# 2021-02-15_HALO_Main_Board.net
KiCad netlist of a schematic drawn in EAGLE
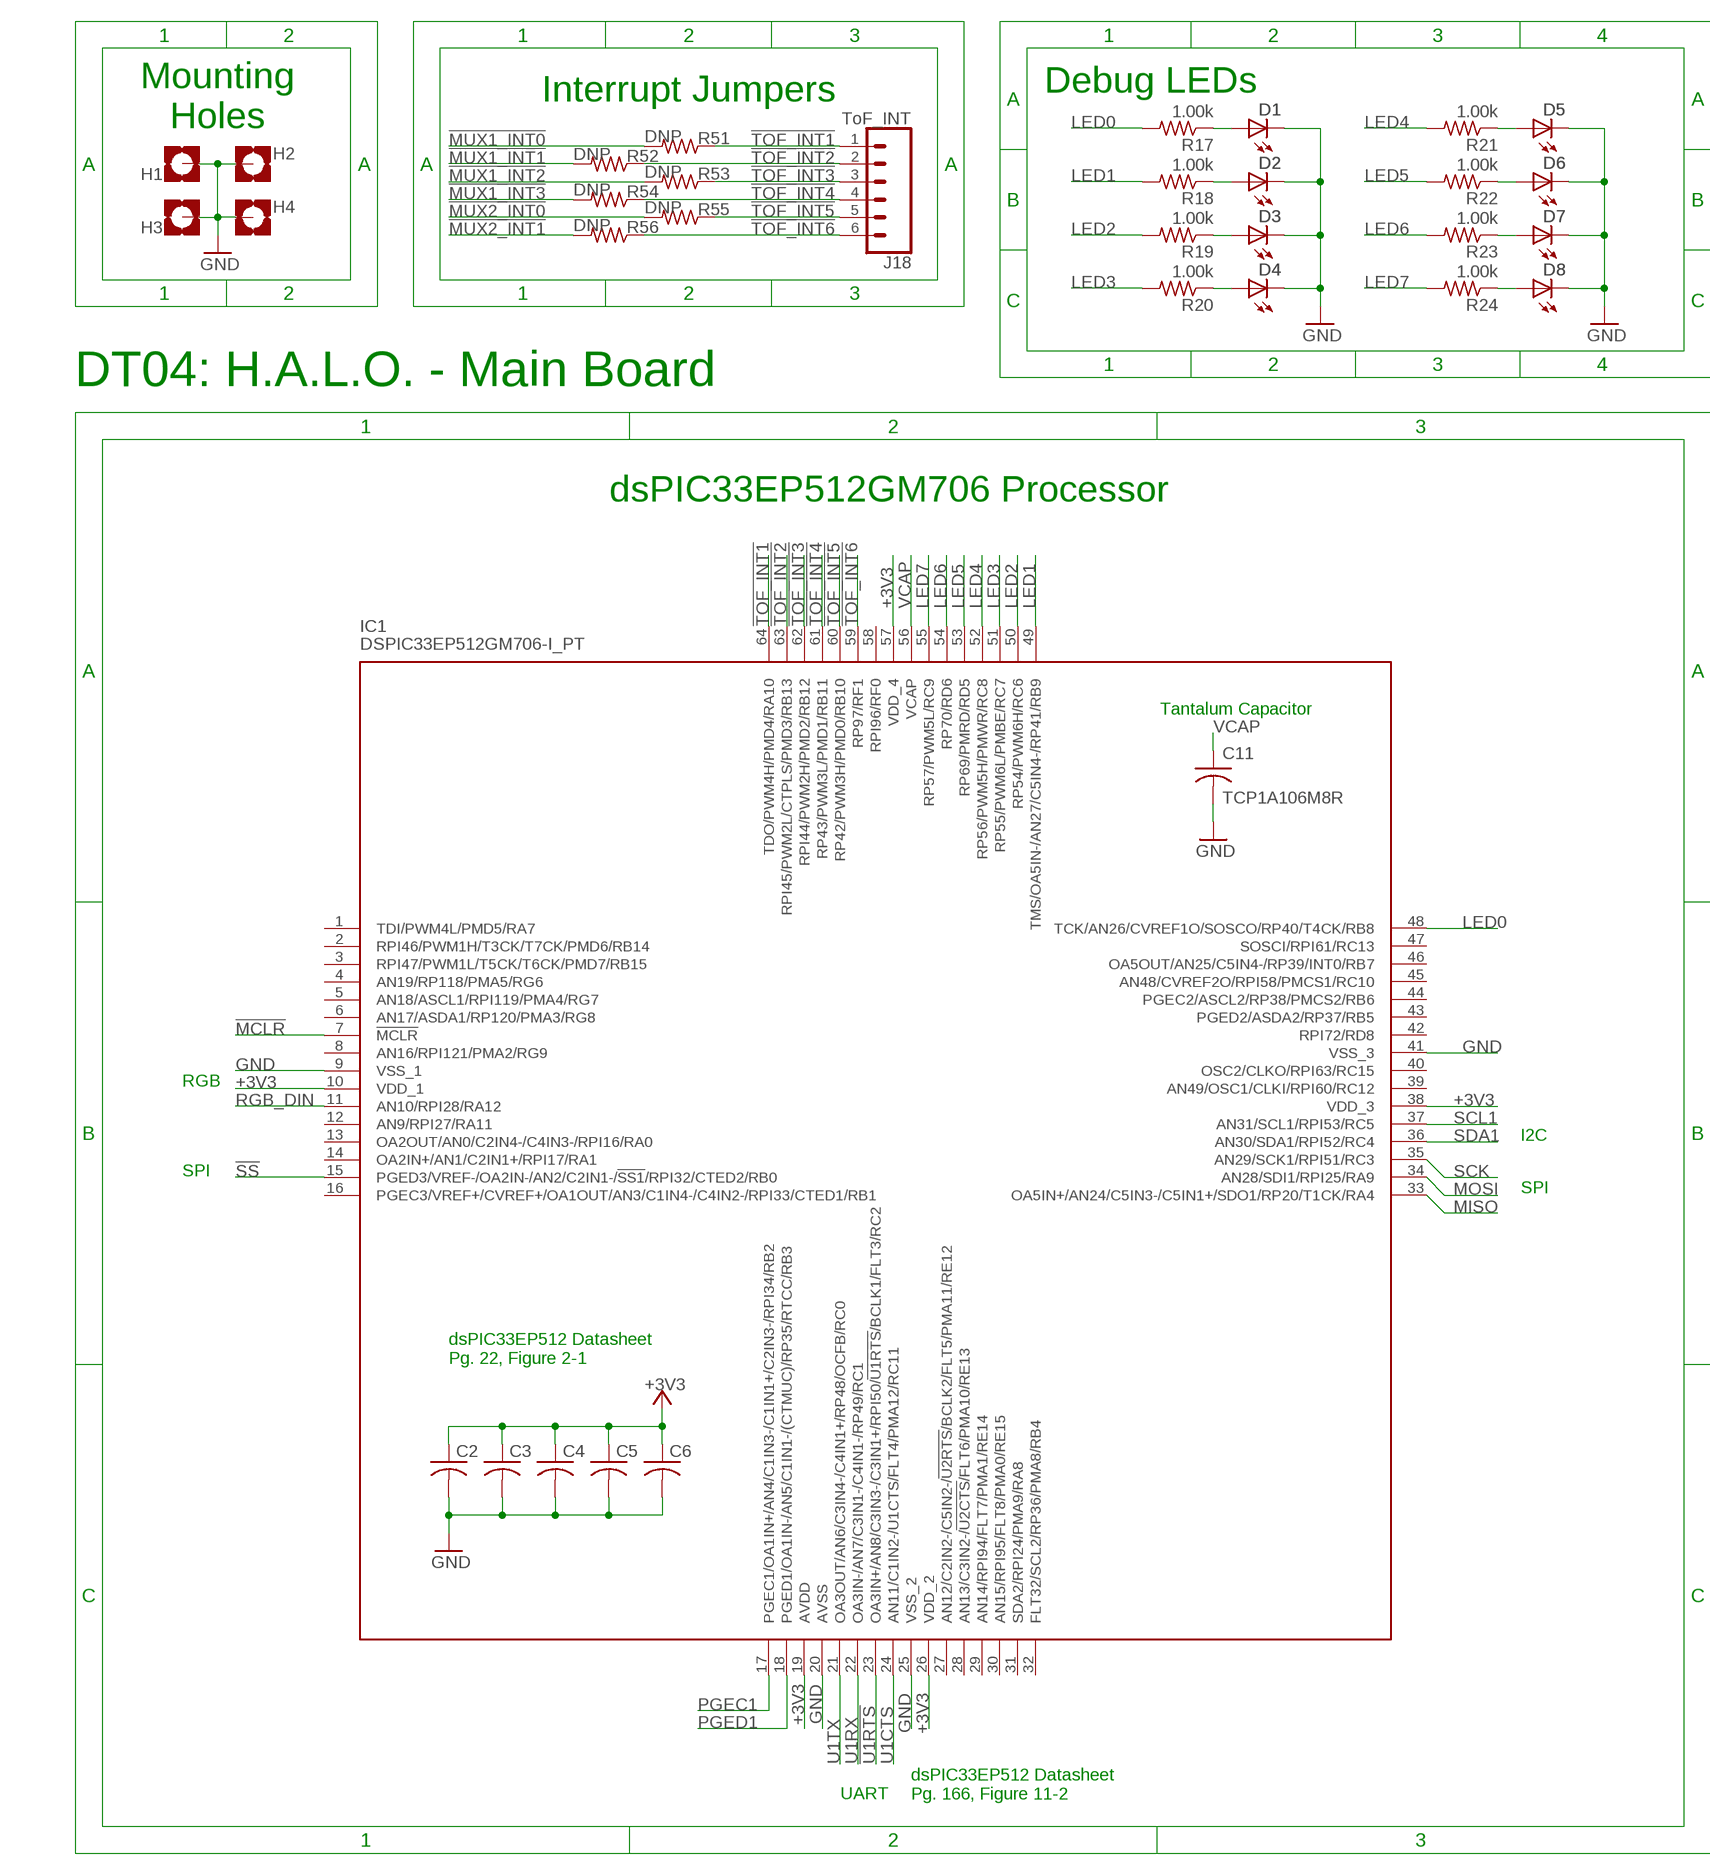
[diagram p0: schematic, sheet 1, part 1 of 2]
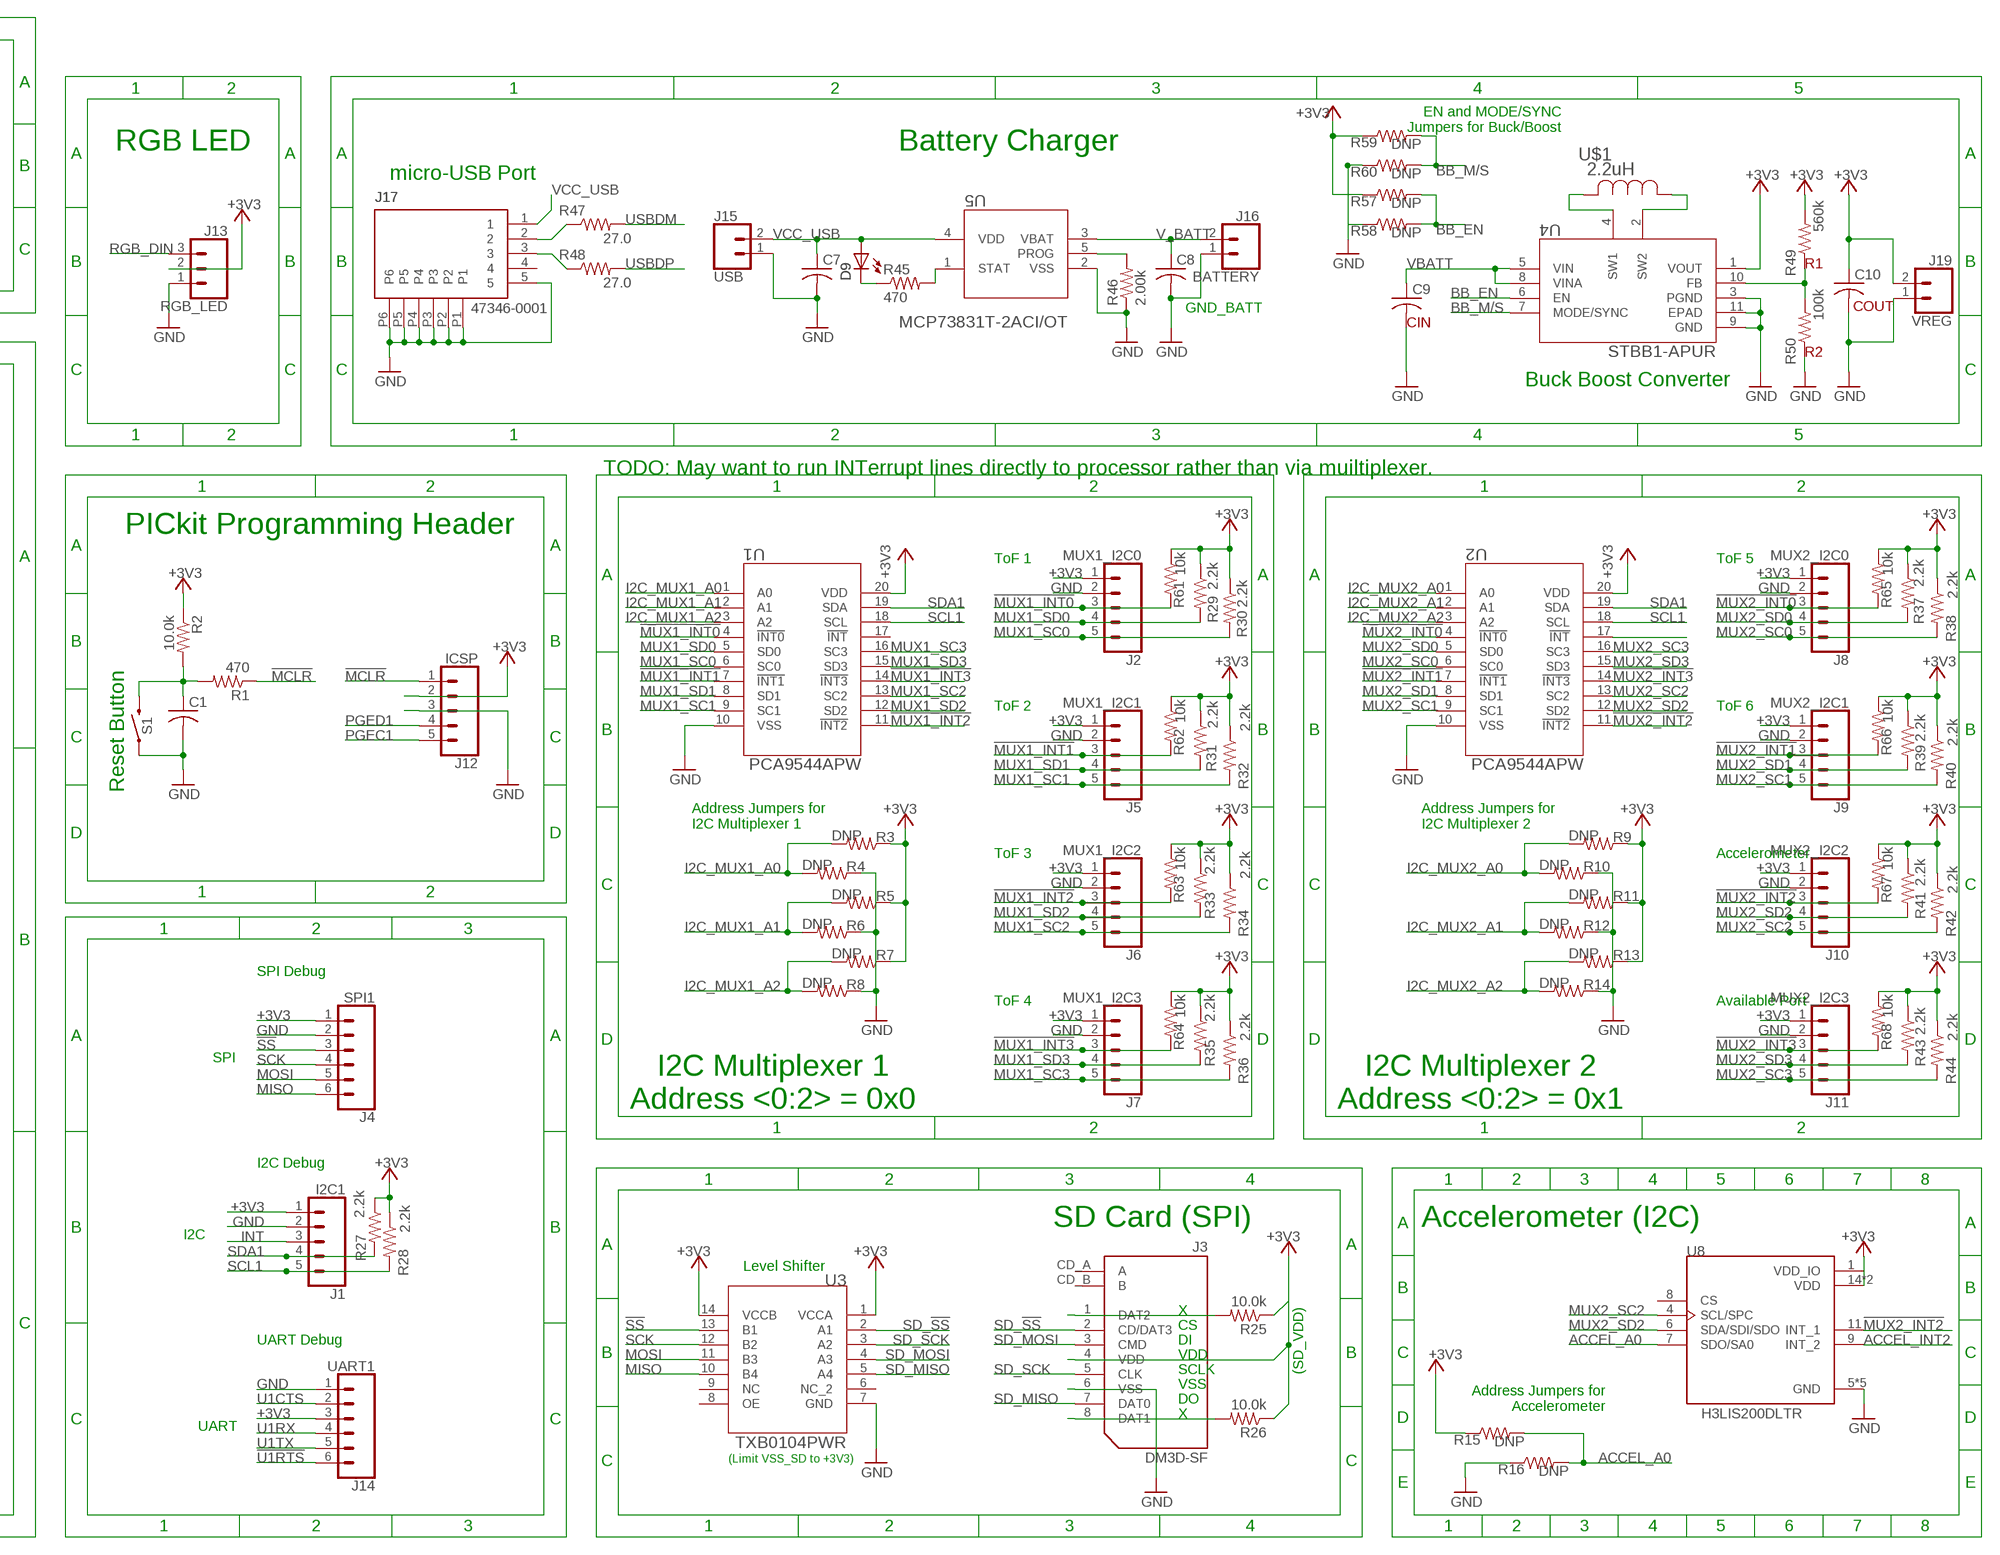
[diagram p1: schematic, sheet 1, part 2 of 2]

(export (version "E")
  (design (tool "Eeschema 10.0.6"))
  (components
    (comp (ref "C1")
      (value "0.1uF")
      (footprint "eagle-import:C0805")
      (libsource (lib "eagle-import") (part "C-USC0805"))
    )
    (comp (ref "C2")
      (value "0.1uF")
      (footprint "eagle-import:C0805")
      (libsource (lib "eagle-import") (part "C-USC0805"))
    )
    (comp (ref "C3")
      (value "0.1uF")
      (footprint "eagle-import:C0805")
      (libsource (lib "eagle-import") (part "C-USC0805"))
    )
    (comp (ref "C4")
      (value "0.1uF")
      (footprint "eagle-import:C0805")
      (libsource (lib "eagle-import") (part "C-USC0805"))
    )
    (comp (ref "C5")
      (value "0.1uF")
      (footprint "eagle-import:C0805")
      (libsource (lib "eagle-import") (part "C-USC0805"))
    )
    (comp (ref "C6")
      (value "0.1uF")
      (footprint "eagle-import:C0805")
      (libsource (lib "eagle-import") (part "C-USC0805"))
    )
    (comp (ref "C7")
      (value "4.7uF")
      (footprint "eagle-import:C0805")
      (libsource (lib "eagle-import") (part "C-USC0805"))
    )
    (comp (ref "C8")
      (value "4.7uF")
      (footprint "eagle-import:C0805")
      (libsource (lib "eagle-import") (part "C-USC0805"))
    )
    (comp (ref "C9")
      (value "10uF")
      (footprint "eagle-import:C0805")
      (libsource (lib "eagle-import") (part "C-USC0805"))
    )
    (comp (ref "C10")
      (value "22uF")
      (footprint "eagle-import:C0805")
      (libsource (lib "eagle-import") (part "C-USC0805"))
    )
    (comp (ref "C11")
      (value "TCP1A106M8R")
      (footprint "eagle-import:TCP_ROM")
      (libsource (lib "eagle-import") (part "TCP1A106M8R"))
    )
    (comp (ref "D1")
      (value "CHIP-LED0805")
      (footprint "eagle-import:CHIP-LED0805")
      (libsource (lib "eagle-import") (part "CHIP-LED0805"))
    )
    (comp (ref "D2")
      (value "CHIP-LED0805")
      (footprint "eagle-import:CHIP-LED0805")
      (libsource (lib "eagle-import") (part "CHIP-LED0805"))
    )
    (comp (ref "D3")
      (value "CHIP-LED0805")
      (footprint "eagle-import:CHIP-LED0805")
      (libsource (lib "eagle-import") (part "CHIP-LED0805"))
    )
    (comp (ref "D4")
      (value "CHIP-LED0805")
      (footprint "eagle-import:CHIP-LED0805")
      (libsource (lib "eagle-import") (part "CHIP-LED0805"))
    )
    (comp (ref "D5")
      (value "CHIP-LED0805")
      (footprint "eagle-import:CHIP-LED0805")
      (libsource (lib "eagle-import") (part "CHIP-LED0805"))
    )
    (comp (ref "D6")
      (value "CHIP-LED0805")
      (footprint "eagle-import:CHIP-LED0805")
      (libsource (lib "eagle-import") (part "CHIP-LED0805"))
    )
    (comp (ref "D7")
      (value "CHIP-LED0805")
      (footprint "eagle-import:CHIP-LED0805")
      (libsource (lib "eagle-import") (part "CHIP-LED0805"))
    )
    (comp (ref "D8")
      (value "CHIP-LED0805")
      (footprint "eagle-import:CHIP-LED0805")
      (libsource (lib "eagle-import") (part "CHIP-LED0805"))
    )
    (comp (ref "D9")
      (value "CHIP-LED0805")
      (footprint "eagle-import:CHIP-LED0805")
      (libsource (lib "eagle-import") (part "CHIP-LED0805"))
    )
    (comp (ref "H1")
      (value "MOUNT-PAD-SQUARE3.0")
      (footprint "eagle-import:3,0-PAD-SQUARE")
      (libsource (lib "eagle-import") (part "MOUNT-PAD-SQUARE3.0"))
    )
    (comp (ref "H2")
      (value "MOUNT-PAD-SQUARE3.0")
      (footprint "eagle-import:3,0-PAD-SQUARE")
      (libsource (lib "eagle-import") (part "MOUNT-PAD-SQUARE3.0"))
    )
    (comp (ref "H3")
      (value "MOUNT-PAD-SQUARE3.0")
      (footprint "eagle-import:3,0-PAD-SQUARE")
      (libsource (lib "eagle-import") (part "MOUNT-PAD-SQUARE3.0"))
    )
    (comp (ref "H4")
      (value "MOUNT-PAD-SQUARE3.0")
      (footprint "eagle-import:3,0-PAD-SQUARE")
      (libsource (lib "eagle-import") (part "MOUNT-PAD-SQUARE3.0"))
    )
    (comp (ref "IC1")
      (value "DSPIC33EP512GM706-I_PT")
      (footprint "eagle-import:QFP50P1200X1200X120-64N")
      (fields
        (field (name "ARROW_PART_NUMBER") "DSPIC33EP512GM706-I/PT")
        (field (name "MOUSER_PART_NUMBER") "579-512GM706-I/PT")
      )
      (libsource (lib "eagle-import") (part "DSPIC33EP512GM706-I_PT"))
    )
    (comp (ref "J1")
      (value "I2C1")
      (footprint "eagle-import:1X05")
      (libsource (lib "eagle-import") (part "CONN_05"))
    )
    (comp (ref "J2")
      (value "MUX1_I2C0")
      (footprint "eagle-import:1X05")
      (libsource (lib "eagle-import") (part "CONN_05"))
    )
    (comp (ref "J3")
      (value "DM3D-SF")
      (footprint "eagle-import:SD_CARD")
      (fields (field (name "PARTNO") "AS-ITM-00047"))
      (libsource (lib "eagle-import") (part "AS-ITM-00047"))
    )
    (comp (ref "J4")
      (value "SPI1")
      (footprint "eagle-import:1X06")
      (libsource (lib "eagle-import") (part "CONN_06SILK_FEMALE_PTH"))
    )
    (comp (ref "J5")
      (value "MUX1_I2C1")
      (footprint "eagle-import:1X05")
      (libsource (lib "eagle-import") (part "CONN_05"))
    )
    (comp (ref "J6")
      (value "MUX1_I2C2")
      (footprint "eagle-import:1X05")
      (libsource (lib "eagle-import") (part "CONN_05"))
    )
    (comp (ref "J7")
      (value "MUX1_I2C3")
      (footprint "eagle-import:1X05")
      (libsource (lib "eagle-import") (part "CONN_05"))
    )
    (comp (ref "J8")
      (value "MUX2_I2C0")
      (footprint "eagle-import:1X05")
      (libsource (lib "eagle-import") (part "CONN_05"))
    )
    (comp (ref "J9")
      (value "MUX2_I2C1")
      (footprint "eagle-import:1X05")
      (libsource (lib "eagle-import") (part "CONN_05"))
    )
    (comp (ref "J10")
      (value "MUX2_I2C2")
      (footprint "eagle-import:1X05")
      (libsource (lib "eagle-import") (part "CONN_05"))
    )
    (comp (ref "J11")
      (value "MUX2_I2C3")
      (footprint "eagle-import:1X05")
      (libsource (lib "eagle-import") (part "CONN_05"))
    )
    (comp (ref "J12")
      (value "ICSP")
      (footprint "eagle-import:1X05")
      (libsource (lib "eagle-import") (part "CONN_05"))
    )
    (comp (ref "J13")
      (value "RGB_LED")
      (footprint "eagle-import:1X03_LOCK")
      (libsource (lib "eagle-import") (part "CONN_03LOCK"))
    )
    (comp (ref "J14")
      (value "UART1")
      (footprint "eagle-import:1X06")
      (libsource (lib "eagle-import") (part "CONN_06SILK_FEMALE_PTH"))
    )
    (comp (ref "J15")
      (value "USB")
      (footprint "eagle-import:1X02")
      (libsource (lib "eagle-import") (part "CONN_02"))
    )
    (comp (ref "J16")
      (value "BATTERY")
      (footprint "eagle-import:1X02")
      (libsource (lib "eagle-import") (part "CONN_02"))
    )
    (comp (ref "J17")
      (value "47346-0001")
      (footprint "eagle-import:MICRO_USB")
      (fields (field (name "PARTNO") "AS-ITM-00021") (field (name "PARTNO_1") "AS-ITM-00021"))
      (libsource (lib "eagle-import") (part "AS-ITM-00021"))
    )
    (comp (ref "J18")
      (value "ToF_INT")
      (footprint "eagle-import:1X06")
      (libsource (lib "eagle-import") (part "CONN_06SILK_FEMALE_PTH"))
    )
    (comp (ref "J19")
      (value "VREG")
      (footprint "eagle-import:1X02")
      (libsource (lib "eagle-import") (part "CONN_02"))
    )
    (comp (ref "R1")
      (value "470")
      (footprint "eagle-import:R0805")
      (libsource (lib "eagle-import") (part "R-US_R0805"))
    )
    (comp (ref "R2")
      (value "10.0k")
      (footprint "eagle-import:R0805")
      (libsource (lib "eagle-import") (part "R-US_R0805"))
    )
    (comp (ref "R3")
      (value "DNP")
      (footprint "eagle-import:R0805")
      (libsource (lib "eagle-import") (part "R-US_R0805"))
    )
    (comp (ref "R4")
      (value "DNP")
      (footprint "eagle-import:R0805")
      (libsource (lib "eagle-import") (part "R-US_R0805"))
    )
    (comp (ref "R5")
      (value "DNP")
      (footprint "eagle-import:R0805")
      (libsource (lib "eagle-import") (part "R-US_R0805"))
    )
    (comp (ref "R6")
      (value "DNP")
      (footprint "eagle-import:R0805")
      (libsource (lib "eagle-import") (part "R-US_R0805"))
    )
    (comp (ref "R7")
      (value "DNP")
      (footprint "eagle-import:R0805")
      (libsource (lib "eagle-import") (part "R-US_R0805"))
    )
    (comp (ref "R8")
      (value "DNP")
      (footprint "eagle-import:R0805")
      (libsource (lib "eagle-import") (part "R-US_R0805"))
    )
    (comp (ref "R9")
      (value "DNP")
      (footprint "eagle-import:R0805")
      (libsource (lib "eagle-import") (part "R-US_R0805"))
    )
    (comp (ref "R10")
      (value "DNP")
      (footprint "eagle-import:R0805")
      (libsource (lib "eagle-import") (part "R-US_R0805"))
    )
    (comp (ref "R11")
      (value "DNP")
      (footprint "eagle-import:R0805")
      (libsource (lib "eagle-import") (part "R-US_R0805"))
    )
    (comp (ref "R12")
      (value "DNP")
      (footprint "eagle-import:R0805")
      (libsource (lib "eagle-import") (part "R-US_R0805"))
    )
    (comp (ref "R13")
      (value "DNP")
      (footprint "eagle-import:R0805")
      (libsource (lib "eagle-import") (part "R-US_R0805"))
    )
    (comp (ref "R14")
      (value "DNP")
      (footprint "eagle-import:R0805")
      (libsource (lib "eagle-import") (part "R-US_R0805"))
    )
    (comp (ref "R15")
      (value "DNP")
      (footprint "eagle-import:R0805")
      (libsource (lib "eagle-import") (part "R-US_R0805"))
    )
    (comp (ref "R16")
      (value "DNP")
      (footprint "eagle-import:R0805")
      (libsource (lib "eagle-import") (part "R-US_R0805"))
    )
    (comp (ref "R17")
      (value "1.00k")
      (footprint "eagle-import:R0805")
      (libsource (lib "eagle-import") (part "R-US_R0805"))
    )
    (comp (ref "R18")
      (value "1.00k")
      (footprint "eagle-import:R0805")
      (libsource (lib "eagle-import") (part "R-US_R0805"))
    )
    (comp (ref "R19")
      (value "1.00k")
      (footprint "eagle-import:R0805")
      (libsource (lib "eagle-import") (part "R-US_R0805"))
    )
    (comp (ref "R20")
      (value "1.00k")
      (footprint "eagle-import:R0805")
      (libsource (lib "eagle-import") (part "R-US_R0805"))
    )
    (comp (ref "R21")
      (value "1.00k")
      (footprint "eagle-import:R0805")
      (libsource (lib "eagle-import") (part "R-US_R0805"))
    )
    (comp (ref "R22")
      (value "1.00k")
      (footprint "eagle-import:R0805")
      (libsource (lib "eagle-import") (part "R-US_R0805"))
    )
    (comp (ref "R23")
      (value "1.00k")
      (footprint "eagle-import:R0805")
      (libsource (lib "eagle-import") (part "R-US_R0805"))
    )
    (comp (ref "R24")
      (value "1.00k")
      (footprint "eagle-import:R0805")
      (libsource (lib "eagle-import") (part "R-US_R0805"))
    )
    (comp (ref "R25")
      (value "10.0k")
      (footprint "eagle-import:R0805")
      (libsource (lib "eagle-import") (part "R-US_R0805"))
    )
    (comp (ref "R26")
      (value "10.0k")
      (footprint "eagle-import:R0805")
      (libsource (lib "eagle-import") (part "R-US_R0805"))
    )
    (comp (ref "R27")
      (value "2.2k")
      (footprint "eagle-import:R0805")
      (libsource (lib "eagle-import") (part "R-US_R0805"))
    )
    (comp (ref "R28")
      (value "2.2k")
      (footprint "eagle-import:R0805")
      (libsource (lib "eagle-import") (part "R-US_R0805"))
    )
    (comp (ref "R29")
      (value "2.2k")
      (footprint "eagle-import:R0805")
      (libsource (lib "eagle-import") (part "R-US_R0805"))
    )
    (comp (ref "R30")
      (value "2.2k")
      (footprint "eagle-import:R0805")
      (libsource (lib "eagle-import") (part "R-US_R0805"))
    )
    (comp (ref "R31")
      (value "2.2k")
      (footprint "eagle-import:R0805")
      (libsource (lib "eagle-import") (part "R-US_R0805"))
    )
    (comp (ref "R32")
      (value "2.2k")
      (footprint "eagle-import:R0805")
      (libsource (lib "eagle-import") (part "R-US_R0805"))
    )
    (comp (ref "R33")
      (value "2.2k")
      (footprint "eagle-import:R0805")
      (libsource (lib "eagle-import") (part "R-US_R0805"))
    )
    (comp (ref "R34")
      (value "2.2k")
      (footprint "eagle-import:R0805")
      (libsource (lib "eagle-import") (part "R-US_R0805"))
    )
    (comp (ref "R35")
      (value "2.2k")
      (footprint "eagle-import:R0805")
      (libsource (lib "eagle-import") (part "R-US_R0805"))
    )
    (comp (ref "R36")
      (value "2.2k")
      (footprint "eagle-import:R0805")
      (libsource (lib "eagle-import") (part "R-US_R0805"))
    )
    (comp (ref "R37")
      (value "2.2k")
      (footprint "eagle-import:R0805")
      (libsource (lib "eagle-import") (part "R-US_R0805"))
    )
    (comp (ref "R38")
      (value "2.2k")
      (footprint "eagle-import:R0805")
      (libsource (lib "eagle-import") (part "R-US_R0805"))
    )
    (comp (ref "R39")
      (value "2.2k")
      (footprint "eagle-import:R0805")
      (libsource (lib "eagle-import") (part "R-US_R0805"))
    )
    (comp (ref "R40")
      (value "2.2k")
      (footprint "eagle-import:R0805")
      (libsource (lib "eagle-import") (part "R-US_R0805"))
    )
    (comp (ref "R41")
      (value "2.2k")
      (footprint "eagle-import:R0805")
      (libsource (lib "eagle-import") (part "R-US_R0805"))
    )
    (comp (ref "R42")
      (value "2.2k")
      (footprint "eagle-import:R0805")
      (libsource (lib "eagle-import") (part "R-US_R0805"))
    )
    (comp (ref "R43")
      (value "2.2k")
      (footprint "eagle-import:R0805")
      (libsource (lib "eagle-import") (part "R-US_R0805"))
    )
    (comp (ref "R44")
      (value "2.2k")
      (footprint "eagle-import:R0805")
      (libsource (lib "eagle-import") (part "R-US_R0805"))
    )
    (comp (ref "R45")
      (value "470")
      (footprint "eagle-import:R0805")
      (libsource (lib "eagle-import") (part "R-US_R0805"))
    )
    (comp (ref "R46")
      (value "2.00k")
      (footprint "eagle-import:R0805")
      (libsource (lib "eagle-import") (part "R-US_R0805"))
    )
    (comp (ref "R47")
      (value "27.0")
      (footprint "eagle-import:R0805")
      (libsource (lib "eagle-import") (part "R-US_R0805"))
    )
    (comp (ref "R48")
      (value "27.0")
      (footprint "eagle-import:R0805")
      (libsource (lib "eagle-import") (part "R-US_R0805"))
    )
    (comp (ref "R49")
      (value "560k")
      (footprint "eagle-import:R0805")
      (libsource (lib "eagle-import") (part "R-US_R0805"))
    )
    (comp (ref "R50")
      (value "100k")
      (footprint "eagle-import:R0805")
      (libsource (lib "eagle-import") (part "R-US_R0805"))
    )
    (comp (ref "R51")
      (value "DNP")
      (footprint "eagle-import:R0805")
      (libsource (lib "eagle-import") (part "R-US_R0805"))
    )
    (comp (ref "R52")
      (value "DNP")
      (footprint "eagle-import:R0805")
      (libsource (lib "eagle-import") (part "R-US_R0805"))
    )
    (comp (ref "R53")
      (value "DNP")
      (footprint "eagle-import:R0805")
      (libsource (lib "eagle-import") (part "R-US_R0805"))
    )
    (comp (ref "R54")
      (value "DNP")
      (footprint "eagle-import:R0805")
      (libsource (lib "eagle-import") (part "R-US_R0805"))
    )
    (comp (ref "R55")
      (value "DNP")
      (footprint "eagle-import:R0805")
      (libsource (lib "eagle-import") (part "R-US_R0805"))
    )
    (comp (ref "R56")
      (value "DNP")
      (footprint "eagle-import:R0805")
      (libsource (lib "eagle-import") (part "R-US_R0805"))
    )
    (comp (ref "R57")
      (value "DNP")
      (footprint "eagle-import:R0805")
      (libsource (lib "eagle-import") (part "R-US_R0805"))
    )
    (comp (ref "R58")
      (value "DNP")
      (footprint "eagle-import:R0805")
      (libsource (lib "eagle-import") (part "R-US_R0805"))
    )
    (comp (ref "R59")
      (value "DNP")
      (footprint "eagle-import:R0805")
      (libsource (lib "eagle-import") (part "R-US_R0805"))
    )
    (comp (ref "R60")
      (value "DNP")
      (footprint "eagle-import:R0805")
      (libsource (lib "eagle-import") (part "R-US_R0805"))
    )
    (comp (ref "R61")
      (value "10k")
      (footprint "eagle-import:R0805")
      (libsource (lib "eagle-import") (part "R-US_R0805"))
    )
    (comp (ref "R62")
      (value "10k")
      (footprint "eagle-import:R0805")
      (libsource (lib "eagle-import") (part "R-US_R0805"))
    )
    (comp (ref "R63")
      (value "10k")
      (footprint "eagle-import:R0805")
      (libsource (lib "eagle-import") (part "R-US_R0805"))
    )
    (comp (ref "R64")
      (value "10k")
      (footprint "eagle-import:R0805")
      (libsource (lib "eagle-import") (part "R-US_R0805"))
    )
    (comp (ref "R65")
      (value "10k")
      (footprint "eagle-import:R0805")
      (libsource (lib "eagle-import") (part "R-US_R0805"))
    )
    (comp (ref "R66")
      (value "10k")
      (footprint "eagle-import:R0805")
      (libsource (lib "eagle-import") (part "R-US_R0805"))
    )
    (comp (ref "R67")
      (value "10k")
      (footprint "eagle-import:R0805")
      (libsource (lib "eagle-import") (part "R-US_R0805"))
    )
    (comp (ref "R68")
      (value "10k")
      (footprint "eagle-import:R0805")
      (libsource (lib "eagle-import") (part "R-US_R0805"))
    )
    (comp (ref "S1")
      (value "SWITCH-MOMENTARY-2SMD-4")
      (footprint "eagle-import:TACTILE_SWITCH_TALL")
      (libsource (lib "eagle-import") (part "SWITCH-MOMENTARY-2SMD-4"))
    )
    (comp (ref "U$1")
      (value "2.2uH")
      (footprint "eagle-import:IND_4028_TDK")
      (libsource (lib "eagle-import") (part "IND"))
    )
    (comp (ref "U1")
      (value "PCA9544APW")
      (footprint "eagle-import:SOT360-1_NXP")
      (libsource (lib "eagle-import") (part "PCA9544APW"))
    )
    (comp (ref "U2")
      (value "PCA9544APW")
      (footprint "eagle-import:SOT360-1_NXP")
      (libsource (lib "eagle-import") (part "PCA9544APW"))
    )
    (comp (ref "U3")
      (value "TXB0104PWR")
      (footprint "eagle-import:PW14")
      (fields
        (field (name "GENERIC_PART_NUMBER") "TXB0104")
        (field (name "MANUFACTURER") "Texas Instruments")
      )
      (libsource (lib "eagle-import") (part "TXB0104PWR"))
    )
    (comp (ref "U4")
      (value "STBB1-APUR")
      (footprint "eagle-import:SON_B1-APUR_STM")
      (libsource (lib "eagle-import") (part "STBB1-APUR"))
    )
    (comp (ref "U5")
      (value "MCP73831T-2ACI/OT")
      (footprint "eagle-import:SOT-23-5_MC_MCH")
      (libsource (lib "eagle-import") (part "MCP73831T-2ACI/OT"))
    )
    (comp (ref "U8")
      (value "H3LIS200DLTR")
      (footprint "eagle-import:PQFN50P300X300X100-16N")
      (fields (field (name "DIGI-KEY_PART_NUMBER") "497-15698-1-ND") (field (name "MF") "STMicroelectronics"))
      (libsource (lib "eagle-import") (part "H3LIS200DLTR"))
    )
  )
  (nets
    (net (code "1") (name "+3V3") (class "Default")
      (node (ref "C10") (pin "1") (pinfunction "1_1") (pintype "passive"))
      (node (ref "C2") (pin "1") (pinfunction "1_1") (pintype "passive"))
      (node (ref "C3") (pin "1") (pinfunction "1_1") (pintype "passive"))
      (node (ref "C4") (pin "1") (pinfunction "1_1") (pintype "passive"))
      (node (ref "C5") (pin "1") (pinfunction "1_1") (pintype "passive"))
      (node (ref "C6") (pin "1") (pinfunction "1_1") (pintype "passive"))
      (node (ref "IC1") (pin "10") (pinfunction "VDD_1_10") (pintype "bidirectional"))
      (node (ref "IC1") (pin "19") (pinfunction "AVDD_19") (pintype "bidirectional"))
      (node (ref "IC1") (pin "26") (pinfunction "VDD_2_26") (pintype "bidirectional"))
      (node (ref "IC1") (pin "38") (pinfunction "VDD_3_38") (pintype "bidirectional"))
      (node (ref "IC1") (pin "57") (pinfunction "VDD_4_57") (pintype "bidirectional"))
      (node (ref "J1") (pin "1") (pinfunction "1_1") (pintype "passive"))
      (node (ref "J10") (pin "1") (pinfunction "1_1") (pintype "passive"))
      (node (ref "J11") (pin "1") (pinfunction "1_1") (pintype "passive"))
      (node (ref "J12") (pin "2") (pinfunction "2_2") (pintype "passive"))
      (node (ref "J13") (pin "2") (pinfunction "2_2") (pintype "passive"))
      (node (ref "J14") (pin "3") (pinfunction "3_3") (pintype "passive"))
      (node (ref "J19") (pin "2") (pinfunction "2_2") (pintype "passive"))
      (node (ref "J2") (pin "1") (pinfunction "1_1") (pintype "passive"))
      (node (ref "J3") (pin "4") (pinfunction "VDD_4") (pintype "bidirectional"))
      (node (ref "J4") (pin "1") (pinfunction "1_1") (pintype "passive"))
      (node (ref "J5") (pin "1") (pinfunction "1_1") (pintype "passive"))
      (node (ref "J6") (pin "1") (pinfunction "1_1") (pintype "passive"))
      (node (ref "J7") (pin "1") (pinfunction "1_1") (pintype "passive"))
      (node (ref "J8") (pin "1") (pinfunction "1_1") (pintype "passive"))
      (node (ref "J9") (pin "1") (pinfunction "1_1") (pintype "passive"))
      (node (ref "R11") (pin "1") (pinfunction "1_1") (pintype "passive"))
      (node (ref "R13") (pin "1") (pinfunction "1_1") (pintype "passive"))
      (node (ref "R15") (pin "1") (pinfunction "1_1") (pintype "passive"))
      (node (ref "R2") (pin "1") (pinfunction "1_1") (pintype "passive"))
      (node (ref "R25") (pin "1") (pinfunction "1_1") (pintype "passive"))
      (node (ref "R26") (pin "1") (pinfunction "1_1") (pintype "passive"))
      (node (ref "R27") (pin "1") (pinfunction "1_1") (pintype "passive"))
      (node (ref "R28") (pin "1") (pinfunction "1_1") (pintype "passive"))
      (node (ref "R29") (pin "1") (pinfunction "1_1") (pintype "passive"))
      (node (ref "R3") (pin "1") (pinfunction "1_1") (pintype "passive"))
      (node (ref "R30") (pin "1") (pinfunction "1_1") (pintype "passive"))
      (node (ref "R31") (pin "1") (pinfunction "1_1") (pintype "passive"))
      (node (ref "R32") (pin "1") (pinfunction "1_1") (pintype "passive"))
      (node (ref "R33") (pin "1") (pinfunction "1_1") (pintype "passive"))
      (node (ref "R34") (pin "1") (pinfunction "1_1") (pintype "passive"))
      (node (ref "R35") (pin "1") (pinfunction "1_1") (pintype "passive"))
      (node (ref "R36") (pin "1") (pinfunction "1_1") (pintype "passive"))
      (node (ref "R37") (pin "1") (pinfunction "1_1") (pintype "passive"))
      (node (ref "R38") (pin "1") (pinfunction "1_1") (pintype "passive"))
      (node (ref "R39") (pin "1") (pinfunction "1_1") (pintype "passive"))
      (node (ref "R40") (pin "1") (pinfunction "1_1") (pintype "passive"))
      (node (ref "R41") (pin "1") (pinfunction "1_1") (pintype "passive"))
      (node (ref "R42") (pin "1") (pinfunction "1_1") (pintype "passive"))
      (node (ref "R43") (pin "1") (pinfunction "1_1") (pintype "passive"))
      (node (ref "R44") (pin "1") (pinfunction "1_1") (pintype "passive"))
      (node (ref "R49") (pin "2") (pinfunction "2_2") (pintype "passive"))
      (node (ref "R5") (pin "1") (pinfunction "1_1") (pintype "passive"))
      (node (ref "R57") (pin "1") (pinfunction "1_1") (pintype "passive"))
      (node (ref "R59") (pin "1") (pinfunction "1_1") (pintype "passive"))
      (node (ref "R61") (pin "1") (pinfunction "1_1") (pintype "passive"))
      (node (ref "R62") (pin "1") (pinfunction "1_1") (pintype "passive"))
      (node (ref "R63") (pin "1") (pinfunction "1_1") (pintype "passive"))
      (node (ref "R64") (pin "1") (pinfunction "1_1") (pintype "passive"))
      (node (ref "R65") (pin "1") (pinfunction "1_1") (pintype "passive"))
      (node (ref "R66") (pin "1") (pinfunction "1_1") (pintype "passive"))
      (node (ref "R67") (pin "1") (pinfunction "1_1") (pintype "passive"))
      (node (ref "R68") (pin "1") (pinfunction "1_1") (pintype "passive"))
      (node (ref "R7") (pin "1") (pinfunction "1_1") (pintype "passive"))
      (node (ref "R9") (pin "1") (pinfunction "1_1") (pintype "passive"))
      (node (ref "U1") (pin "20") (pinfunction "VDD_20") (pintype "passive"))
      (node (ref "U2") (pin "20") (pinfunction "VDD_20") (pintype "passive"))
      (node (ref "U3") (pin "1") (pinfunction "VCCA_1") (pintype "power_in"))
      (node (ref "U3") (pin "14") (pinfunction "VCCB_14") (pintype "power_in"))
      (node (ref "U4") (pin "1") (pinfunction "VOUT_1") (pintype "power_in"))
      (node (ref "U8") (pin "1") (pinfunction "VDD_IO_1") (pintype "power_in"))
      (node (ref "U8") (pin "14") (pinfunction "VDD_14") (pintype "power_in"))
      (node (ref "U8") (pin "15") (pinfunction "VDD_15") (pintype "power_in"))
    )
    (net (code "2") (name "/ACCEL_A0") (class "Default")
      (node (ref "R15") (pin "2") (pinfunction "2_2") (pintype "passive"))
      (node (ref "R16") (pin "2") (pinfunction "2_2") (pintype "passive"))
      (node (ref "U8") (pin "7") (pinfunction "SDO/SA0_7") (pintype "output"))
    )
    (net (code "3") (name "/ACCEL_INT2") (class "Default")
      (node (ref "U8") (pin "9") (pinfunction "INT_2_9") (pintype "output"))
    )
    (net (code "4") (name "/BB_EN") (class "Default")
      (node (ref "R57") (pin "2") (pinfunction "2_2") (pintype "passive"))
      (node (ref "R58") (pin "2") (pinfunction "2_2") (pintype "passive"))
      (node (ref "U4") (pin "6") (pinfunction "EN_6") (pintype "passive"))
    )
    (net (code "5") (name "/BB_M{slash}S") (class "Default")
      (node (ref "R59") (pin "2") (pinfunction "2_2") (pintype "passive"))
      (node (ref "R60") (pin "2") (pinfunction "2_2") (pintype "passive"))
      (node (ref "U4") (pin "7") (pinfunction "MODE/SYNC_7") (pintype "passive"))
    )
    (net (code "6") (name "/I2C_MUX1_A0") (class "Default")
      (node (ref "R3") (pin "2") (pinfunction "2_2") (pintype "passive"))
      (node (ref "R4") (pin "2") (pinfunction "2_2") (pintype "passive"))
      (node (ref "U1") (pin "1") (pinfunction "A0_1") (pintype "passive"))
    )
    (net (code "7") (name "/I2C_MUX1_A1") (class "Default")
      (node (ref "R5") (pin "2") (pinfunction "2_2") (pintype "passive"))
      (node (ref "R6") (pin "2") (pinfunction "2_2") (pintype "passive"))
      (node (ref "U1") (pin "2") (pinfunction "A1_2") (pintype "passive"))
    )
    (net (code "8") (name "/I2C_MUX1_A2") (class "Default")
      (node (ref "R7") (pin "2") (pinfunction "2_2") (pintype "passive"))
      (node (ref "R8") (pin "2") (pinfunction "2_2") (pintype "passive"))
      (node (ref "U1") (pin "3") (pinfunction "A2_3") (pintype "passive"))
    )
    (net (code "9") (name "/I2C_MUX2_A0") (class "Default")
      (node (ref "R10") (pin "2") (pinfunction "2_2") (pintype "passive"))
      (node (ref "R9") (pin "2") (pinfunction "2_2") (pintype "passive"))
      (node (ref "U2") (pin "1") (pinfunction "A0_1") (pintype "passive"))
    )
    (net (code "10") (name "/I2C_MUX2_A1") (class "Default")
      (node (ref "R11") (pin "2") (pinfunction "2_2") (pintype "passive"))
      (node (ref "R12") (pin "2") (pinfunction "2_2") (pintype "passive"))
      (node (ref "U2") (pin "2") (pinfunction "A1_2") (pintype "passive"))
    )
    (net (code "11") (name "/I2C_MUX2_A2") (class "Default")
      (node (ref "R13") (pin "2") (pinfunction "2_2") (pintype "passive"))
      (node (ref "R14") (pin "2") (pinfunction "2_2") (pintype "passive"))
      (node (ref "U2") (pin "3") (pinfunction "A2_3") (pintype "passive"))
    )
    (net (code "12") (name "/INT") (class "Default")
      (node (ref "J1") (pin "3") (pinfunction "3_3") (pintype "passive"))
    )
    (net (code "13") (name "/LED0") (class "Default")
      (node (ref "IC1") (pin "48") (pinfunction "TCK/AN26/CVREF1O/SOSCO/RP40/T4CK/RB8_48") (pintype "bidirectional"))
      (node (ref "R17") (pin "2") (pinfunction "2_2") (pintype "passive"))
    )
    (net (code "14") (name "/LED1") (class "Default")
      (node (ref "IC1") (pin "49") (pinfunction "TMS/OA5IN-/AN27/C5IN4-/RP41/RB9_49") (pintype "bidirectional"))
      (node (ref "R18") (pin "2") (pinfunction "2_2") (pintype "passive"))
    )
    (net (code "15") (name "/LED2") (class "Default")
      (node (ref "IC1") (pin "50") (pinfunction "RP54/PWM6H/RC6_50") (pintype "bidirectional"))
      (node (ref "R19") (pin "2") (pinfunction "2_2") (pintype "passive"))
    )
    (net (code "16") (name "/LED3") (class "Default")
      (node (ref "IC1") (pin "51") (pinfunction "RP55/PWM6L/PMBE/RC7_51") (pintype "bidirectional"))
      (node (ref "R20") (pin "2") (pinfunction "2_2") (pintype "passive"))
    )
    (net (code "17") (name "/LED4") (class "Default")
      (node (ref "IC1") (pin "52") (pinfunction "RP56/PWM5H/PMWR/RC8_52") (pintype "bidirectional"))
      (node (ref "R21") (pin "2") (pinfunction "2_2") (pintype "passive"))
    )
    (net (code "18") (name "/LED5") (class "Default")
      (node (ref "IC1") (pin "53") (pinfunction "RP69/PMRD/RD5_53") (pintype "bidirectional"))
      (node (ref "R22") (pin "2") (pinfunction "2_2") (pintype "passive"))
    )
    (net (code "19") (name "/LED6") (class "Default")
      (node (ref "IC1") (pin "54") (pinfunction "RP70/RD6_54") (pintype "bidirectional"))
      (node (ref "R23") (pin "2") (pinfunction "2_2") (pintype "passive"))
    )
    (net (code "20") (name "/LED7") (class "Default")
      (node (ref "IC1") (pin "55") (pinfunction "RP57/PWM5L/RC9_55") (pintype "bidirectional"))
      (node (ref "R24") (pin "2") (pinfunction "2_2") (pintype "passive"))
    )
    (net (code "21") (name "/MISO") (class "Default")
      (node (ref "IC1") (pin "33") (pinfunction "OA5IN+/AN24/C5IN3-/C5IN1+/SDO1/RP20/T1CK/RA4_33") (pintype "bidirectional"))
      (node (ref "J4") (pin "6") (pinfunction "6_6") (pintype "passive"))
      (node (ref "U3") (pin "10") (pinfunction "B4_10") (pintype "bidirectional"))
    )
    (net (code "22") (name "/MOSI") (class "Default")
      (node (ref "IC1") (pin "34") (pinfunction "AN28/SDI1/RPI25/RA9_34") (pintype "bidirectional"))
      (node (ref "J4") (pin "5") (pinfunction "5_5") (pintype "passive"))
      (node (ref "U3") (pin "11") (pinfunction "B3_11") (pintype "bidirectional"))
    )
    (net (code "23") (name "/MUX1_SC0") (class "Default")
      (node (ref "J2") (pin "5") (pinfunction "5_5") (pintype "passive"))
      (node (ref "R30") (pin "2") (pinfunction "2_2") (pintype "passive"))
      (node (ref "U1") (pin "6") (pinfunction "SC0_6") (pintype "passive"))
    )
    (net (code "24") (name "/MUX1_SC1") (class "Default")
      (node (ref "J5") (pin "5") (pinfunction "5_5") (pintype "passive"))
      (node (ref "R32") (pin "2") (pinfunction "2_2") (pintype "passive"))
      (node (ref "U1") (pin "9") (pinfunction "SC1_9") (pintype "passive"))
    )
    (net (code "25") (name "/MUX1_SC2") (class "Default")
      (node (ref "J6") (pin "5") (pinfunction "5_5") (pintype "passive"))
      (node (ref "R34") (pin "2") (pinfunction "2_2") (pintype "passive"))
      (node (ref "U1") (pin "13") (pinfunction "SC2_13") (pintype "passive"))
    )
    (net (code "26") (name "/MUX1_SC3") (class "Default")
      (node (ref "J7") (pin "5") (pinfunction "5_5") (pintype "passive"))
      (node (ref "R36") (pin "2") (pinfunction "2_2") (pintype "passive"))
      (node (ref "U1") (pin "16") (pinfunction "SC3_16") (pintype "passive"))
    )
    (net (code "27") (name "/MUX1_SD0") (class "Default")
      (node (ref "J2") (pin "4") (pinfunction "4_4") (pintype "passive"))
      (node (ref "R29") (pin "2") (pinfunction "2_2") (pintype "passive"))
      (node (ref "U1") (pin "5") (pinfunction "SD0_5") (pintype "passive"))
    )
    (net (code "28") (name "/MUX1_SD1") (class "Default")
      (node (ref "J5") (pin "4") (pinfunction "4_4") (pintype "passive"))
      (node (ref "R31") (pin "2") (pinfunction "2_2") (pintype "passive"))
      (node (ref "U1") (pin "8") (pinfunction "SD1_8") (pintype "passive"))
    )
    (net (code "29") (name "/MUX1_SD2") (class "Default")
      (node (ref "J6") (pin "4") (pinfunction "4_4") (pintype "passive"))
      (node (ref "R33") (pin "2") (pinfunction "2_2") (pintype "passive"))
      (node (ref "U1") (pin "12") (pinfunction "SD2_12") (pintype "passive"))
    )
    (net (code "30") (name "/MUX1_SD3") (class "Default")
      (node (ref "J7") (pin "4") (pinfunction "4_4") (pintype "passive"))
      (node (ref "R35") (pin "2") (pinfunction "2_2") (pintype "passive"))
      (node (ref "U1") (pin "15") (pinfunction "SD3_15") (pintype "passive"))
    )
    (net (code "31") (name "/MUX2_SC0") (class "Default")
      (node (ref "J8") (pin "5") (pinfunction "5_5") (pintype "passive"))
      (node (ref "R38") (pin "2") (pinfunction "2_2") (pintype "passive"))
      (node (ref "U2") (pin "6") (pinfunction "SC0_6") (pintype "passive"))
    )
    (net (code "32") (name "/MUX2_SC1") (class "Default")
      (node (ref "J9") (pin "5") (pinfunction "5_5") (pintype "passive"))
      (node (ref "R40") (pin "2") (pinfunction "2_2") (pintype "passive"))
      (node (ref "U2") (pin "9") (pinfunction "SC1_9") (pintype "passive"))
    )
    (net (code "33") (name "/MUX2_SC2") (class "Default")
      (node (ref "J10") (pin "5") (pinfunction "5_5") (pintype "passive"))
      (node (ref "R42") (pin "2") (pinfunction "2_2") (pintype "passive"))
      (node (ref "U2") (pin "13") (pinfunction "SC2_13") (pintype "passive"))
      (node (ref "U8") (pin "4") (pinfunction "SCL/SPC_4") (pintype "input"))
    )
    (net (code "34") (name "/MUX2_SC3") (class "Default")
      (node (ref "J11") (pin "5") (pinfunction "5_5") (pintype "passive"))
      (node (ref "R44") (pin "2") (pinfunction "2_2") (pintype "passive"))
      (node (ref "U2") (pin "16") (pinfunction "SC3_16") (pintype "passive"))
    )
    (net (code "35") (name "/MUX2_SD0") (class "Default")
      (node (ref "J8") (pin "4") (pinfunction "4_4") (pintype "passive"))
      (node (ref "R37") (pin "2") (pinfunction "2_2") (pintype "passive"))
      (node (ref "U2") (pin "5") (pinfunction "SD0_5") (pintype "passive"))
    )
    (net (code "36") (name "/MUX2_SD1") (class "Default")
      (node (ref "J9") (pin "4") (pinfunction "4_4") (pintype "passive"))
      (node (ref "R39") (pin "2") (pinfunction "2_2") (pintype "passive"))
      (node (ref "U2") (pin "8") (pinfunction "SD1_8") (pintype "passive"))
    )
    (net (code "37") (name "/MUX2_SD2") (class "Default")
      (node (ref "J10") (pin "4") (pinfunction "4_4") (pintype "passive"))
      (node (ref "R41") (pin "2") (pinfunction "2_2") (pintype "passive"))
      (node (ref "U2") (pin "12") (pinfunction "SD2_12") (pintype "passive"))
      (node (ref "U8") (pin "6") (pinfunction "SDA/SDI/SDO_6") (pintype "bidirectional"))
    )
    (net (code "38") (name "/MUX2_SD3") (class "Default")
      (node (ref "J11") (pin "4") (pinfunction "4_4") (pintype "passive"))
      (node (ref "R43") (pin "2") (pinfunction "2_2") (pintype "passive"))
      (node (ref "U2") (pin "15") (pinfunction "SD3_15") (pintype "passive"))
    )
    (net (code "39") (name "/PGEC1") (class "Default")
      (node (ref "IC1") (pin "17") (pinfunction "PGEC1/OA1IN+/AN4/C1IN3-/C1IN1+/C2IN3-/RPI34/RB2_17") (pintype "bidirectional"))
      (node (ref "J12") (pin "5") (pinfunction "5_5") (pintype "passive"))
    )
    (net (code "40") (name "/PGED1") (class "Default")
      (node (ref "IC1") (pin "18") (pinfunction "PGED1/OA1IN-/AN5/C1IN1-/(CTMUC)/RP35/RTCC/RB3_18") (pintype "bidirectional"))
      (node (ref "J12") (pin "4") (pinfunction "4_4") (pintype "passive"))
    )
    (net (code "41") (name "/RGB_DIN") (class "Default")
      (node (ref "IC1") (pin "11") (pinfunction "AN10/RPI28/RA12_11") (pintype "bidirectional"))
      (node (ref "J13") (pin "3") (pinfunction "3_3") (pintype "passive"))
    )
    (net (code "42") (name "/SCK") (class "Default")
      (node (ref "IC1") (pin "35") (pinfunction "AN29/SCK1/RPI51/RC3_35") (pintype "bidirectional"))
      (node (ref "J4") (pin "4") (pinfunction "4_4") (pintype "passive"))
      (node (ref "U3") (pin "12") (pinfunction "B2_12") (pintype "bidirectional"))
    )
    (net (code "43") (name "/SCL1") (class "Default")
      (node (ref "IC1") (pin "37") (pinfunction "AN31/SCL1/RPI53/RC5_37") (pintype "bidirectional"))
      (node (ref "J1") (pin "5") (pinfunction "5_5") (pintype "passive"))
      (node (ref "R28") (pin "2") (pinfunction "2_2") (pintype "passive"))
      (node (ref "U1") (pin "18") (pinfunction "SCL_18") (pintype "passive"))
      (node (ref "U2") (pin "18") (pinfunction "SCL_18") (pintype "passive"))
    )
    (net (code "44") (name "/SDA1") (class "Default")
      (node (ref "IC1") (pin "36") (pinfunction "AN30/SDA1/RPI52/RC4_36") (pintype "bidirectional"))
      (node (ref "J1") (pin "4") (pinfunction "4_4") (pintype "passive"))
      (node (ref "R27") (pin "2") (pinfunction "2_2") (pintype "passive"))
      (node (ref "U1") (pin "19") (pinfunction "SDA_19") (pintype "passive"))
      (node (ref "U2") (pin "19") (pinfunction "SDA_19") (pintype "passive"))
    )
    (net (code "45") (name "/SD_MISO") (class "Default")
      (node (ref "J3") (pin "7") (pinfunction "DAT0_7") (pintype "bidirectional"))
      (node (ref "U3") (pin "5") (pinfunction "A4_5") (pintype "bidirectional"))
    )
    (net (code "46") (name "/SD_MOSI") (class "Default")
      (node (ref "J3") (pin "3") (pinfunction "CMD_3") (pintype "bidirectional"))
      (node (ref "U3") (pin "4") (pinfunction "A3_4") (pintype "bidirectional"))
    )
    (net (code "47") (name "/SD_SCK") (class "Default")
      (node (ref "J3") (pin "5") (pinfunction "CLK_5") (pintype "bidirectional"))
      (node (ref "U3") (pin "3") (pinfunction "A2_3") (pintype "bidirectional"))
    )
    (net (code "48") (name "/SD_~{SS}") (class "Default")
      (node (ref "J3") (pin "2") (pinfunction "CD/DAT3_2") (pintype "bidirectional"))
      (node (ref "U3") (pin "2") (pinfunction "A1_2") (pintype "bidirectional"))
    )
    (net (code "49") (name "/U1CTS") (class "Default")
      (node (ref "IC1") (pin "24") (pinfunction "AN11/C1IN2-/U1CTS/FLT4/PMA12/RC11_24") (pintype "bidirectional"))
      (node (ref "J14") (pin "2") (pinfunction "2_2") (pintype "passive"))
    )
    (net (code "50") (name "/U1RX") (class "Default")
      (node (ref "IC1") (pin "22") (pinfunction "OA3IN-/AN7/C3IN1-/C4IN1-/RP49/RC1_22") (pintype "bidirectional"))
      (node (ref "J14") (pin "4") (pinfunction "4_4") (pintype "passive"))
    )
    (net (code "51") (name "/U1TX") (class "Default")
      (node (ref "IC1") (pin "21") (pinfunction "OA3OUT/AN6/C3IN4-/C4IN1+/RP48/OCFB/RC0_21") (pintype "bidirectional"))
      (node (ref "J14") (pin "5") (pinfunction "5_5") (pintype "passive"))
    )
    (net (code "52") (name "/USBDM") (class "Default")
      (node (ref "R47") (pin "2") (pinfunction "2_2") (pintype "passive"))
    )
    (net (code "53") (name "/USBDP") (class "Default")
      (node (ref "R48") (pin "2") (pinfunction "2_2") (pintype "passive"))
    )
    (net (code "54") (name "/VBATT") (class "Default")
      (node (ref "C9") (pin "1") (pinfunction "1_1") (pintype "passive"))
      (node (ref "U4") (pin "5") (pinfunction "VIN_5") (pintype "power_in"))
      (node (ref "U4") (pin "8") (pinfunction "VINA_8") (pintype "power_in"))
    )
    (net (code "55") (name "/VCAP") (class "Default")
      (node (ref "C11") (pin "1") (pinfunction "1_1") (pintype "passive"))
      (node (ref "IC1") (pin "56") (pinfunction "VCAP_56") (pintype "bidirectional"))
    )
    (net (code "56") (name "/VCC_USB") (class "Default")
      (node (ref "C7") (pin "1") (pinfunction "1_1") (pintype "passive"))
      (node (ref "D9") (pin "A") (pinfunction "A_A") (pintype "passive"))
      (node (ref "J15") (pin "2") (pinfunction "2_2") (pintype "passive"))
      (node (ref "J17") (pin "1") (pinfunction "1_1") (pintype "bidirectional"))
      (node (ref "U5") (pin "4") (pinfunction "VDD_4") (pintype "passive"))
    )
    (net (code "57") (name "/V_BATT") (class "Default")
      (node (ref "C8") (pin "1") (pinfunction "1_1") (pintype "passive"))
      (node (ref "J16") (pin "2") (pinfunction "2_2") (pintype "passive"))
      (node (ref "U5") (pin "3") (pinfunction "VBAT_3") (pintype "passive"))
    )
    (net (code "58") (name "/~{MCLR}") (class "Default")
      (node (ref "IC1") (pin "7") (pinfunction "~{MCLR}_7") (pintype "bidirectional"))
      (node (ref "J12") (pin "1") (pinfunction "1_1") (pintype "passive"))
      (node (ref "R1") (pin "1") (pinfunction "1_1") (pintype "passive"))
    )
    (net (code "59") (name "/~{MUX1_INT0}") (class "Default")
      (node (ref "J2") (pin "3") (pinfunction "3_3") (pintype "passive"))
      (node (ref "R51") (pin "2") (pinfunction "2_2") (pintype "passive"))
      (node (ref "R61") (pin "2") (pinfunction "2_2") (pintype "passive"))
      (node (ref "U1") (pin "4") (pinfunction "~{INT0}_4") (pintype "passive"))
    )
    (net (code "60") (name "/~{MUX1_INT1}") (class "Default")
      (node (ref "J5") (pin "3") (pinfunction "3_3") (pintype "passive"))
      (node (ref "R52") (pin "2") (pinfunction "2_2") (pintype "passive"))
      (node (ref "R62") (pin "2") (pinfunction "2_2") (pintype "passive"))
      (node (ref "U1") (pin "7") (pinfunction "~{INT1}_7") (pintype "passive"))
    )
    (net (code "61") (name "/~{MUX1_INT2}") (class "Default")
      (node (ref "J6") (pin "3") (pinfunction "3_3") (pintype "passive"))
      (node (ref "R53") (pin "2") (pinfunction "2_2") (pintype "passive"))
      (node (ref "R63") (pin "2") (pinfunction "2_2") (pintype "passive"))
      (node (ref "U1") (pin "11") (pinfunction "~{INT2}_11") (pintype "passive"))
    )
    (net (code "62") (name "/~{MUX1_INT3}") (class "Default")
      (node (ref "J7") (pin "3") (pinfunction "3_3") (pintype "passive"))
      (node (ref "R54") (pin "2") (pinfunction "2_2") (pintype "passive"))
      (node (ref "R64") (pin "2") (pinfunction "2_2") (pintype "passive"))
      (node (ref "U1") (pin "14") (pinfunction "~{INT3}_14") (pintype "passive"))
    )
    (net (code "63") (name "/~{MUX2_INT0}") (class "Default")
      (node (ref "J8") (pin "3") (pinfunction "3_3") (pintype "passive"))
      (node (ref "R55") (pin "2") (pinfunction "2_2") (pintype "passive"))
      (node (ref "R65") (pin "2") (pinfunction "2_2") (pintype "passive"))
      (node (ref "U2") (pin "4") (pinfunction "~{INT0}_4") (pintype "passive"))
    )
    (net (code "64") (name "/~{MUX2_INT1}") (class "Default")
      (node (ref "J9") (pin "3") (pinfunction "3_3") (pintype "passive"))
      (node (ref "R56") (pin "2") (pinfunction "2_2") (pintype "passive"))
      (node (ref "R66") (pin "2") (pinfunction "2_2") (pintype "passive"))
      (node (ref "U2") (pin "7") (pinfunction "~{INT1}_7") (pintype "passive"))
    )
    (net (code "65") (name "/~{MUX2_INT2}") (class "Default")
      (node (ref "J10") (pin "3") (pinfunction "3_3") (pintype "passive"))
      (node (ref "R67") (pin "2") (pinfunction "2_2") (pintype "passive"))
      (node (ref "U2") (pin "11") (pinfunction "~{INT2}_11") (pintype "passive"))
      (node (ref "U8") (pin "11") (pinfunction "INT_1_11") (pintype "output"))
    )
    (net (code "66") (name "/~{MUX2_INT3}") (class "Default")
      (node (ref "J11") (pin "3") (pinfunction "3_3") (pintype "passive"))
      (node (ref "R68") (pin "2") (pinfunction "2_2") (pintype "passive"))
      (node (ref "U2") (pin "14") (pinfunction "~{INT3}_14") (pintype "passive"))
    )
    (net (code "67") (name "/~{SS}") (class "Default")
      (node (ref "IC1") (pin "15") (pinfunction "PGED3/VREF-/OA2IN-/AN2/C2IN1-/~{SS1}/RPI32/CTED2/RB0_15") (pintype "bidirectional"))
      (node (ref "J4") (pin "3") (pinfunction "3_3") (pintype "passive"))
      (node (ref "U3") (pin "13") (pinfunction "B1_13") (pintype "bidirectional"))
    )
    (net (code "68") (name "/~{TOF_INT1}") (class "Default")
      (node (ref "IC1") (pin "64") (pinfunction "TDO/PWM4H/PMD4/RA10_64") (pintype "bidirectional"))
      (node (ref "J18") (pin "1") (pinfunction "1_1") (pintype "passive"))
      (node (ref "R51") (pin "1") (pinfunction "1_1") (pintype "passive"))
    )
    (net (code "69") (name "/~{TOF_INT2}") (class "Default")
      (node (ref "IC1") (pin "63") (pinfunction "RPI45/PWM2L/CTPLS/PMD3/RB13_63") (pintype "bidirectional"))
      (node (ref "J18") (pin "2") (pinfunction "2_2") (pintype "passive"))
      (node (ref "R52") (pin "1") (pinfunction "1_1") (pintype "passive"))
    )
    (net (code "70") (name "/~{TOF_INT3}") (class "Default")
      (node (ref "IC1") (pin "62") (pinfunction "RPI44/PWM2H/PMD2/RB12_62") (pintype "bidirectional"))
      (node (ref "J18") (pin "3") (pinfunction "3_3") (pintype "passive"))
      (node (ref "R53") (pin "1") (pinfunction "1_1") (pintype "passive"))
    )
    (net (code "71") (name "/~{TOF_INT4}") (class "Default")
      (node (ref "IC1") (pin "61") (pinfunction "RP43/PWM3L/PMD1/RB11_61") (pintype "bidirectional"))
      (node (ref "J18") (pin "4") (pinfunction "4_4") (pintype "passive"))
      (node (ref "R54") (pin "1") (pinfunction "1_1") (pintype "passive"))
    )
    (net (code "72") (name "/~{TOF_INT5}") (class "Default")
      (node (ref "IC1") (pin "60") (pinfunction "RP42/PWM3H/PMD0/RB10_60") (pintype "bidirectional"))
      (node (ref "J18") (pin "5") (pinfunction "5_5") (pintype "passive"))
      (node (ref "R55") (pin "1") (pinfunction "1_1") (pintype "passive"))
    )
    (net (code "73") (name "/~{TOF_INT6}") (class "Default")
      (node (ref "IC1") (pin "59") (pinfunction "RP97/RF1_59") (pintype "bidirectional"))
      (node (ref "J18") (pin "6") (pinfunction "6_6") (pintype "passive"))
      (node (ref "R56") (pin "1") (pinfunction "1_1") (pintype "passive"))
    )
    (net (code "74") (name "/~{U1RTS}") (class "Default")
      (node (ref "IC1") (pin "23") (pinfunction "OA3IN+/AN8/C3IN3-/C3IN1+/RPI50/~{U1RTS}/BCLK1/FLT3/RC2_23") (pintype "bidirectional"))
      (node (ref "J14") (pin "6") (pinfunction "6_6") (pintype "passive"))
    )
    (net (code "75") (name "GND") (class "Default")
      (node (ref "C1") (pin "2") (pinfunction "2_2") (pintype "passive"))
      (node (ref "C10") (pin "2") (pinfunction "2_2") (pintype "passive"))
      (node (ref "C11") (pin "2") (pinfunction "2_2") (pintype "passive"))
      (node (ref "C2") (pin "2") (pinfunction "2_2") (pintype "passive"))
      (node (ref "C3") (pin "2") (pinfunction "2_2") (pintype "passive"))
      (node (ref "C4") (pin "2") (pinfunction "2_2") (pintype "passive"))
      (node (ref "C5") (pin "2") (pinfunction "2_2") (pintype "passive"))
      (node (ref "C6") (pin "2") (pinfunction "2_2") (pintype "passive"))
      (node (ref "C7") (pin "2") (pinfunction "2_2") (pintype "passive"))
      (node (ref "C8") (pin "2") (pinfunction "2_2") (pintype "passive"))
      (node (ref "C9") (pin "2") (pinfunction "2_2") (pintype "passive"))
      (node (ref "D1") (pin "C") (pinfunction "C_C") (pintype "passive"))
      (node (ref "D2") (pin "C") (pinfunction "C_C") (pintype "passive"))
      (node (ref "D3") (pin "C") (pinfunction "C_C") (pintype "passive"))
      (node (ref "D4") (pin "C") (pinfunction "C_C") (pintype "passive"))
      (node (ref "D5") (pin "C") (pinfunction "C_C") (pintype "passive"))
      (node (ref "D6") (pin "C") (pinfunction "C_C") (pintype "passive"))
      (node (ref "D7") (pin "C") (pinfunction "C_C") (pintype "passive"))
      (node (ref "D8") (pin "C") (pinfunction "C_C") (pintype "passive"))
      (node (ref "H1") (pin "B3,0") (pinfunction "MOUNT_B3,0") (pintype "passive"))
      (node (ref "H2") (pin "B3,0") (pinfunction "MOUNT_B3,0") (pintype "passive"))
      (node (ref "H3") (pin "B3,0") (pinfunction "MOUNT_B3,0") (pintype "passive"))
      (node (ref "H4") (pin "B3,0") (pinfunction "MOUNT_B3,0") (pintype "passive"))
      (node (ref "IC1") (pin "20") (pinfunction "AVSS_20") (pintype "bidirectional"))
      (node (ref "IC1") (pin "25") (pinfunction "VSS_2_25") (pintype "bidirectional"))
      (node (ref "IC1") (pin "41") (pinfunction "VSS_3_41") (pintype "bidirectional"))
      (node (ref "IC1") (pin "9") (pinfunction "VSS_1_9") (pintype "bidirectional"))
      (node (ref "J1") (pin "2") (pinfunction "2_2") (pintype "passive"))
      (node (ref "J10") (pin "2") (pinfunction "2_2") (pintype "passive"))
      (node (ref "J11") (pin "2") (pinfunction "2_2") (pintype "passive"))
      (node (ref "J12") (pin "3") (pinfunction "3_3") (pintype "passive"))
      (node (ref "J13") (pin "1") (pinfunction "1_1") (pintype "passive"))
      (node (ref "J14") (pin "1") (pinfunction "1_1") (pintype "passive"))
      (node (ref "J15") (pin "1") (pinfunction "1_1") (pintype "passive"))
      (node (ref "J16") (pin "1") (pinfunction "1_1") (pintype "passive"))
      (node (ref "J17") (pin "5") (pinfunction "5_5") (pintype "bidirectional"))
      (node (ref "J17") (pin "P1") (pinfunction "P1_P1") (pintype "bidirectional"))
      (node (ref "J17") (pin "P2") (pinfunction "P2_P2") (pintype "bidirectional"))
      (node (ref "J17") (pin "P3") (pinfunction "P3_P3") (pintype "bidirectional"))
      (node (ref "J17") (pin "P4") (pinfunction "P4_P4") (pintype "bidirectional"))
      (node (ref "J17") (pin "P5") (pinfunction "P5_P5") (pintype "bidirectional"))
      (node (ref "J17") (pin "P6") (pinfunction "P6_P6") (pintype "bidirectional"))
      (node (ref "J19") (pin "1") (pinfunction "1_1") (pintype "passive"))
      (node (ref "J2") (pin "2") (pinfunction "2_2") (pintype "passive"))
      (node (ref "J3") (pin "6") (pinfunction "VSS_6") (pintype "bidirectional"))
      (node (ref "J4") (pin "2") (pinfunction "2_2") (pintype "passive"))
      (node (ref "J5") (pin "2") (pinfunction "2_2") (pintype "passive"))
      (node (ref "J6") (pin "2") (pinfunction "2_2") (pintype "passive"))
      (node (ref "J7") (pin "2") (pinfunction "2_2") (pintype "passive"))
      (node (ref "J8") (pin "2") (pinfunction "2_2") (pintype "passive"))
      (node (ref "J9") (pin "2") (pinfunction "2_2") (pintype "passive"))
      (node (ref "R10") (pin "1") (pinfunction "1_1") (pintype "passive"))
      (node (ref "R12") (pin "1") (pinfunction "1_1") (pintype "passive"))
      (node (ref "R14") (pin "1") (pinfunction "1_1") (pintype "passive"))
      (node (ref "R16") (pin "1") (pinfunction "1_1") (pintype "passive"))
      (node (ref "R4") (pin "1") (pinfunction "1_1") (pintype "passive"))
      (node (ref "R46") (pin "1") (pinfunction "1_1") (pintype "passive"))
      (node (ref "R50") (pin "1") (pinfunction "1_1") (pintype "passive"))
      (node (ref "R58") (pin "1") (pinfunction "1_1") (pintype "passive"))
      (node (ref "R6") (pin "1") (pinfunction "1_1") (pintype "passive"))
      (node (ref "R60") (pin "1") (pinfunction "1_1") (pintype "passive"))
      (node (ref "R8") (pin "1") (pinfunction "1_1") (pintype "passive"))
      (node (ref "S1") (pin "A2") (pinfunction "1_A2") (pintype "passive"))
      (node (ref "U1") (pin "10") (pinfunction "VSS_10") (pintype "passive"))
      (node (ref "U2") (pin "10") (pinfunction "VSS_10") (pintype "passive"))
      (node (ref "U3") (pin "7") (pinfunction "GND_7") (pintype "power_in"))
      (node (ref "U4") (pin "11") (pinfunction "EPAD_11") (pintype "passive"))
      (node (ref "U4") (pin "3") (pinfunction "PGND_3") (pintype "passive"))
      (node (ref "U4") (pin "9") (pinfunction "GND_9") (pintype "passive"))
      (node (ref "U5") (pin "2") (pinfunction "VSS_2") (pintype "passive"))
      (node (ref "U8") (pin "10") (pinfunction "GND_10") (pintype "power_in"))
      (node (ref "U8") (pin "12") (pinfunction "GND_12") (pintype "power_in"))
      (node (ref "U8") (pin "13") (pinfunction "GND_13") (pintype "power_in"))
      (node (ref "U8") (pin "16") (pinfunction "GND_16") (pintype "power_in"))
      (node (ref "U8") (pin "5") (pinfunction "GND_5") (pintype "power_in"))
    )
    (net (code "76") (name "Net-(D1-PadA)") (class "Default")
      (node (ref "D1") (pin "A") (pinfunction "A_A") (pintype "passive"))
      (node (ref "R17") (pin "1") (pinfunction "1_1") (pintype "passive"))
    )
    (net (code "77") (name "Net-(D2-PadA)") (class "Default")
      (node (ref "D2") (pin "A") (pinfunction "A_A") (pintype "passive"))
      (node (ref "R18") (pin "1") (pinfunction "1_1") (pintype "passive"))
    )
    (net (code "78") (name "Net-(D3-PadA)") (class "Default")
      (node (ref "D3") (pin "A") (pinfunction "A_A") (pintype "passive"))
      (node (ref "R19") (pin "1") (pinfunction "1_1") (pintype "passive"))
    )
    (net (code "79") (name "Net-(D4-PadA)") (class "Default")
      (node (ref "D4") (pin "A") (pinfunction "A_A") (pintype "passive"))
      (node (ref "R20") (pin "1") (pinfunction "1_1") (pintype "passive"))
    )
    (net (code "80") (name "Net-(D5-PadA)") (class "Default")
      (node (ref "D5") (pin "A") (pinfunction "A_A") (pintype "passive"))
      (node (ref "R21") (pin "1") (pinfunction "1_1") (pintype "passive"))
    )
    (net (code "81") (name "Net-(D6-PadA)") (class "Default")
      (node (ref "D6") (pin "A") (pinfunction "A_A") (pintype "passive"))
      (node (ref "R22") (pin "1") (pinfunction "1_1") (pintype "passive"))
    )
    (net (code "82") (name "Net-(D7-PadA)") (class "Default")
      (node (ref "D7") (pin "A") (pinfunction "A_A") (pintype "passive"))
      (node (ref "R23") (pin "1") (pinfunction "1_1") (pintype "passive"))
    )
    (net (code "83") (name "Net-(D8-PadA)") (class "Default")
      (node (ref "D8") (pin "A") (pinfunction "A_A") (pintype "passive"))
      (node (ref "R24") (pin "1") (pinfunction "1_1") (pintype "passive"))
    )
    (net (code "84") (name "Net-(D9-PadC)") (class "Default")
      (node (ref "D9") (pin "C") (pinfunction "C_C") (pintype "passive"))
      (node (ref "R45") (pin "1") (pinfunction "1_1") (pintype "passive"))
    )
    (net (code "85") (name "Net-(J3-DAT1)") (class "Default")
      (node (ref "J3") (pin "8") (pinfunction "DAT1_8") (pintype "bidirectional"))
      (node (ref "R26") (pin "2") (pinfunction "2_2") (pintype "passive"))
    )
    (net (code "86") (name "Net-(J3-DAT2)") (class "Default")
      (node (ref "J3") (pin "1") (pinfunction "DAT2_1") (pintype "bidirectional"))
      (node (ref "R25") (pin "2") (pinfunction "2_2") (pintype "passive"))
    )
    (net (code "87") (name "Net-(J17-Pad2)") (class "Default")
      (node (ref "J17") (pin "2") (pinfunction "2_2") (pintype "bidirectional"))
      (node (ref "R47") (pin "1") (pinfunction "1_1") (pintype "passive"))
    )
    (net (code "88") (name "Net-(J17-Pad3)") (class "Default")
      (node (ref "J17") (pin "3") (pinfunction "3_3") (pintype "bidirectional"))
      (node (ref "R48") (pin "1") (pinfunction "1_1") (pintype "passive"))
    )
    (net (code "89") (name "Net-(S1-2)") (class "Default")
      (node (ref "C1") (pin "1") (pinfunction "1_1") (pintype "passive"))
      (node (ref "R1") (pin "2") (pinfunction "2_2") (pintype "passive"))
      (node (ref "R2") (pin "2") (pinfunction "2_2") (pintype "passive"))
      (node (ref "S1") (pin "B2") (pinfunction "2_B2") (pintype "passive"))
    )
    (net (code "90") (name "Net-(U4-FB)") (class "Default")
      (node (ref "R49") (pin "1") (pinfunction "1_1") (pintype "passive"))
      (node (ref "R50") (pin "2") (pinfunction "2_2") (pintype "passive"))
      (node (ref "U4") (pin "10") (pinfunction "FB_10") (pintype "passive"))
    )
    (net (code "91") (name "Net-(U4-SW1)") (class "Default")
      (node (ref "U$1") (pin "2") (pinfunction "2_2") (pintype "passive"))
      (node (ref "U4") (pin "4") (pinfunction "SW1_4") (pintype "bidirectional"))
    )
    (net (code "92") (name "Net-(U4-SW2)") (class "Default")
      (node (ref "U$1") (pin "1") (pinfunction "1_1") (pintype "passive"))
      (node (ref "U4") (pin "2") (pinfunction "SW2_2") (pintype "bidirectional"))
    )
    (net (code "93") (name "Net-(U5-PROG)") (class "Default")
      (node (ref "R46") (pin "2") (pinfunction "2_2") (pintype "passive"))
      (node (ref "U5") (pin "5") (pinfunction "PROG_5") (pintype "passive"))
    )
    (net (code "94") (name "Net-(U5-STAT)") (class "Default")
      (node (ref "R45") (pin "2") (pinfunction "2_2") (pintype "passive"))
      (node (ref "U5") (pin "1") (pinfunction "STAT_1") (pintype "passive"))
    )
    (net (code "95") (name "unconnected-(IC1-AN9{slash}RPI27{slash}RA11-Pad12)") (class "Default")
      (node (ref "IC1") (pin "12") (pinfunction "AN9/RPI27/RA11_12") (pintype "bidirectional"))
    )
    (net (code "96") (name "unconnected-(IC1-AN12{slash}C2IN2-{slash}C5IN2-{slash}~{U2RTS}{slash}BCLK2{slash}FLT5{slash}PMA11{slash}RE12-Pad27)") (class "Default")
      (node (ref "IC1") (pin "27") (pinfunction "AN12/C2IN2-/C5IN2-/~{U2RTS}/BCLK2/FLT5/PMA11/RE12_27") (pintype "bidirectional"))
    )
    (net (code "97") (name "unconnected-(IC1-AN13{slash}C3IN2-{slash}~{U2CTS}{slash}FLT6{slash}PMA10{slash}RE13-Pad28)") (class "Default")
      (node (ref "IC1") (pin "28") (pinfunction "AN13/C3IN2-/~{U2CTS}/FLT6/PMA10/RE13_28") (pintype "bidirectional"))
    )
    (net (code "98") (name "unconnected-(IC1-AN14{slash}RPI94{slash}FLT7{slash}PMA1{slash}RE14-Pad29)") (class "Default")
      (node (ref "IC1") (pin "29") (pinfunction "AN14/RPI94/FLT7/PMA1/RE14_29") (pintype "bidirectional"))
    )
    (net (code "99") (name "unconnected-(IC1-AN15{slash}RPI95{slash}FLT8{slash}PMA0{slash}RE15-Pad30)") (class "Default")
      (node (ref "IC1") (pin "30") (pinfunction "AN15/RPI95/FLT8/PMA0/RE15_30") (pintype "bidirectional"))
    )
    (net (code "100") (name "unconnected-(IC1-AN16{slash}RPI121{slash}PMA2{slash}RG9-Pad8)") (class "Default")
      (node (ref "IC1") (pin "8") (pinfunction "AN16/RPI121/PMA2/RG9_8") (pintype "bidirectional"))
    )
    (net (code "101") (name "unconnected-(IC1-AN17{slash}ASDA1{slash}RP120{slash}PMA3{slash}RG8-Pad6)") (class "Default")
      (node (ref "IC1") (pin "6") (pinfunction "AN17/ASDA1/RP120/PMA3/RG8_6") (pintype "bidirectional"))
    )
    (net (code "102") (name "unconnected-(IC1-AN18{slash}ASCL1{slash}RPI119{slash}PMA4{slash}RG7-Pad5)") (class "Default")
      (node (ref "IC1") (pin "5") (pinfunction "AN18/ASCL1/RPI119/PMA4/RG7_5") (pintype "bidirectional"))
    )
    (net (code "103") (name "unconnected-(IC1-AN19{slash}RP118{slash}PMA5{slash}RG6-Pad4)") (class "Default")
      (node (ref "IC1") (pin "4") (pinfunction "AN19/RP118/PMA5/RG6_4") (pintype "bidirectional"))
    )
    (net (code "104") (name "unconnected-(IC1-AN48{slash}CVREF2O{slash}RPI58{slash}PMCS1{slash}RC10-Pad45)") (class "Default")
      (node (ref "IC1") (pin "45") (pinfunction "AN48/CVREF2O/RPI58/PMCS1/RC10_45") (pintype "bidirectional"))
    )
    (net (code "105") (name "unconnected-(IC1-AN49{slash}OSC1{slash}CLKI{slash}RPI60{slash}RC12-Pad39)") (class "Default")
      (node (ref "IC1") (pin "39") (pinfunction "AN49/OSC1/CLKI/RPI60/RC12_39") (pintype "bidirectional"))
    )
    (net (code "106") (name "unconnected-(IC1-FLT32{slash}SCL2{slash}RP36{slash}PMA8{slash}RB4-Pad32)") (class "Default")
      (node (ref "IC1") (pin "32") (pinfunction "FLT32/SCL2/RP36/PMA8/RB4_32") (pintype "bidirectional"))
    )
    (net (code "107") (name "unconnected-(IC1-OA2IN+{slash}AN1{slash}C2IN1+{slash}RPI17{slash}RA1-Pad14)") (class "Default")
      (node (ref "IC1") (pin "14") (pinfunction "OA2IN+/AN1/C2IN1+/RPI17/RA1_14") (pintype "bidirectional"))
    )
    (net (code "108") (name "unconnected-(IC1-OA2OUT{slash}AN0{slash}C2IN4-{slash}C4IN3-{slash}RPI16{slash}RA0-Pad13)") (class "Default")
      (node (ref "IC1") (pin "13") (pinfunction "OA2OUT/AN0/C2IN4-/C4IN3-/RPI16/RA0_13") (pintype "bidirectional"))
    )
    (net (code "109") (name "unconnected-(IC1-OA5OUT{slash}AN25{slash}C5IN4-{slash}RP39{slash}INT0{slash}RB7-Pad46)") (class "Default")
      (node (ref "IC1") (pin "46") (pinfunction "OA5OUT/AN25/C5IN4-/RP39/INT0/RB7_46") (pintype "bidirectional"))
    )
    (net (code "110") (name "unconnected-(IC1-OSC2{slash}CLKO{slash}RPI63{slash}RC15-Pad40)") (class "Default")
      (node (ref "IC1") (pin "40") (pinfunction "OSC2/CLKO/RPI63/RC15_40") (pintype "bidirectional"))
    )
    (net (code "111") (name "unconnected-(IC1-PGEC2{slash}ASCL2{slash}RP38{slash}PMCS2{slash}RB6-Pad44)") (class "Default")
      (node (ref "IC1") (pin "44") (pinfunction "PGEC2/ASCL2/RP38/PMCS2/RB6_44") (pintype "bidirectional"))
    )
    (net (code "112") (name "unconnected-(IC1-PGEC3{slash}VREF+{slash}CVREF+{slash}OA1OUT{slash}AN3{slash}C1IN4-{slash}C4IN2-{slash}RPI33{slash}CTED1{slash}RB1-Pad16)") (class "Default")
      (node (ref "IC1") (pin "16") (pinfunction "PGEC3/VREF+/CVREF+/OA1OUT/AN3/C1IN4-/C4IN2-/RPI33/CTED1/RB1_16") (pintype "bidirectional"))
    )
    (net (code "113") (name "unconnected-(IC1-PGED2{slash}ASDA2{slash}RP37{slash}RB5-Pad43)") (class "Default")
      (node (ref "IC1") (pin "43") (pinfunction "PGED2/ASDA2/RP37/RB5_43") (pintype "bidirectional"))
    )
    (net (code "114") (name "unconnected-(IC1-RPI46{slash}PWM1H{slash}T3CK{slash}T7CK{slash}PMD6{slash}RB14-Pad2)") (class "Default")
      (node (ref "IC1") (pin "2") (pinfunction "RPI46/PWM1H/T3CK/T7CK/PMD6/RB14_2") (pintype "bidirectional"))
    )
    (net (code "115") (name "unconnected-(IC1-RPI47{slash}PWM1L{slash}T5CK{slash}T6CK{slash}PMD7{slash}RB15-Pad3)") (class "Default")
      (node (ref "IC1") (pin "3") (pinfunction "RPI47/PWM1L/T5CK/T6CK/PMD7/RB15_3") (pintype "bidirectional"))
    )
    (net (code "116") (name "unconnected-(IC1-RPI72{slash}RD8-Pad42)") (class "Default")
      (node (ref "IC1") (pin "42") (pinfunction "RPI72/RD8_42") (pintype "bidirectional"))
    )
    (net (code "117") (name "unconnected-(IC1-RPI96{slash}RF0-Pad58)") (class "Default")
      (node (ref "IC1") (pin "58") (pinfunction "RPI96/RF0_58") (pintype "bidirectional"))
    )
    (net (code "118") (name "unconnected-(IC1-SDA2{slash}RPI24{slash}PMA9{slash}RA8-Pad31)") (class "Default")
      (node (ref "IC1") (pin "31") (pinfunction "SDA2/RPI24/PMA9/RA8_31") (pintype "bidirectional"))
    )
    (net (code "119") (name "unconnected-(IC1-SOSCI{slash}RPI61{slash}RC13-Pad47)") (class "Default")
      (node (ref "IC1") (pin "47") (pinfunction "SOSCI/RPI61/RC13_47") (pintype "bidirectional"))
    )
    (net (code "120") (name "unconnected-(IC1-TDI{slash}PWM4L{slash}PMD5{slash}RA7-Pad1)") (class "Default")
      (node (ref "IC1") (pin "1") (pinfunction "TDI/PWM4L/PMD5/RA7_1") (pintype "bidirectional"))
    )
    (net (code "121") (name "unconnected-(J3-A-PadCD_A)") (class "Default")
      (node (ref "J3") (pin "CD_A") (pinfunction "A_CD_A") (pintype "bidirectional"))
    )
    (net (code "122") (name "unconnected-(J3-B-PadCD_B)") (class "Default")
      (node (ref "J3") (pin "CD_B") (pinfunction "B_CD_B") (pintype "bidirectional"))
    )
    (net (code "123") (name "unconnected-(J17-Pad4)") (class "Default")
      (node (ref "J17") (pin "4") (pinfunction "4_4") (pintype "bidirectional"))
    )
    (net (code "124") (name "unconnected-(U1-~{INT}-Pad17)") (class "Default")
      (node (ref "U1") (pin "17") (pinfunction "~{INT}_17") (pintype "passive"))
    )
    (net (code "125") (name "unconnected-(U2-~{INT}-Pad17)") (class "Default")
      (node (ref "U2") (pin "17") (pinfunction "~{INT}_17") (pintype "passive"))
    )
    (net (code "126") (name "unconnected-(U3-NC-Pad9)") (class "Default")
      (node (ref "U3") (pin "9") (pinfunction "NC_9") (pintype "passive"))
    )
    (net (code "127") (name "unconnected-(U3-NC_2-Pad6)") (class "Default")
      (node (ref "U3") (pin "6") (pinfunction "NC_2_6") (pintype "passive"))
    )
    (net (code "128") (name "unconnected-(U3-OE-Pad8)") (class "Default")
      (node (ref "U3") (pin "8") (pinfunction "OE_8") (pintype "output"))
    )
    (net (code "129") (name "unconnected-(U8-CS-Pad8)") (class "Default")
      (node (ref "U8") (pin "8") (pinfunction "CS_8") (pintype "input"))
    )
  )
)
